# charger-breakout.net
KiCad netlist of a schematic drawn in EAGLE
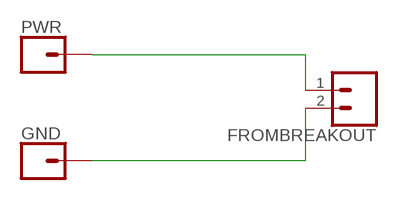
[diagram p0: schematic, sheet 1]

(export (version "E")
  (design (tool "Eeschema 10.0.6"))
  (components
    (comp (ref "FROMBREAKOUT")
      (value "CONN_021X02_NO_SILK")
      (footprint "eagle-import:1X02_NO_SILK")
      (libsource (lib "eagle-import") (part "CONN_021X02_NO_SILK"))
    )
    (comp (ref "GND")
      (value "CONN_01SNAP-FEMALE")
      (footprint "eagle-import:SNAP-FEMALE")
      (libsource (lib "eagle-import") (part "CONN_01SNAP-FEMALE"))
    )
    (comp (ref "PWR")
      (value "CONN_01SNAP-FEMALE")
      (footprint "eagle-import:SNAP-FEMALE")
      (libsource (lib "eagle-import") (part "CONN_01SNAP-FEMALE"))
    )
  )
  (nets
    (net (code "1") (name "Net-(FROMBREAKOUT-Pad1)") (class "Default")
      (node (ref "FROMBREAKOUT") (pin "1") (pinfunction "1_1") (pintype "passive"))
      (node (ref "PWR") (pin "1") (pinfunction "1_1") (pintype "passive"))
    )
    (net (code "2") (name "Net-(FROMBREAKOUT-Pad2)") (class "Default")
      (node (ref "FROMBREAKOUT") (pin "2") (pinfunction "2_2") (pintype "passive"))
      (node (ref "GND") (pin "1") (pinfunction "1_1") (pintype "passive"))
    )
  )
)
